# currentHack.net
KiCad netlist of a schematic drawn in EAGLE
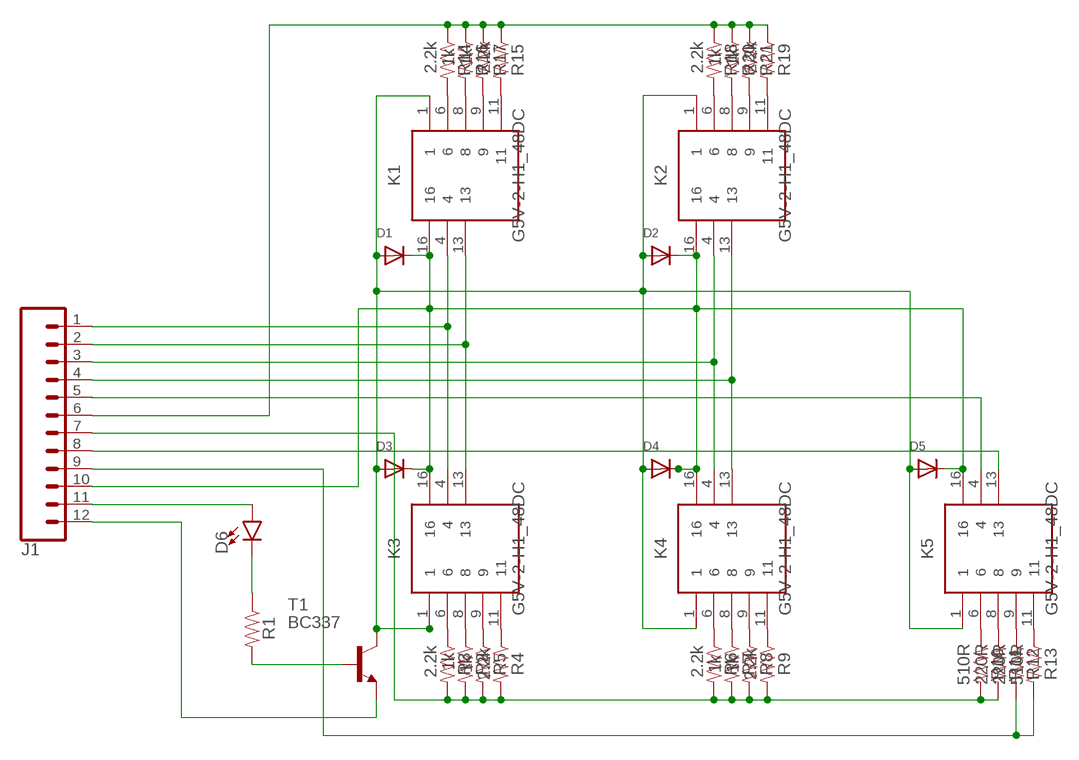
[diagram p0: schematic, sheet 1]

(export (version "E")
  (design (tool "Eeschema 10.0.6"))
  (components
    (comp (ref "D1")
      (value "DIODEDO-1N4148")
      (footprint "eagle-import:DO-1N4148")
      (libsource (lib "eagle-import") (part "DIODEDO-1N4148"))
    )
    (comp (ref "D2")
      (value "DIODEDO-1N4148")
      (footprint "eagle-import:DO-1N4148")
      (libsource (lib "eagle-import") (part "DIODEDO-1N4148"))
    )
    (comp (ref "D3")
      (value "DIODEDO-1N4148")
      (footprint "eagle-import:DO-1N4148")
      (libsource (lib "eagle-import") (part "DIODEDO-1N4148"))
    )
    (comp (ref "D4")
      (value "DIODEDO-1N4148")
      (footprint "eagle-import:DO-1N4148")
      (libsource (lib "eagle-import") (part "DIODEDO-1N4148"))
    )
    (comp (ref "D5")
      (value "DIODEDO-1N4148")
      (footprint "eagle-import:DO-1N4148")
      (libsource (lib "eagle-import") (part "DIODEDO-1N4148"))
    )
    (comp (ref "D6")
      (value "LED3MM")
      (footprint "eagle-import:LED_3MM")
      (libsource (lib "eagle-import") (part "LED3MM"))
    )
    (comp (ref "J1")
      (value "CONN_12")
      (footprint "eagle-import:1X12")
      (libsource (lib "eagle-import") (part "CONN_12"))
    )
    (comp (ref "K1")
      (value "G5V-2-H1_48DC")
      (footprint "eagle-import:G5V-2-H1")
      (fields
        (field (name "MANUFACTURER_PART_NUMBER") "G5V-2-H1 48DC")
        (field (name "RS_PART_NUMBER") "6839270P")
      )
      (libsource (lib "eagle-import") (part "G5V-2-H1_48DC"))
    )
    (comp (ref "K2")
      (value "G5V-2-H1_48DC")
      (footprint "eagle-import:G5V-2-H1")
      (fields
        (field (name "MANUFACTURER_PART_NUMBER") "G5V-2-H1 48DC")
        (field (name "RS_PART_NUMBER") "6839270P")
      )
      (libsource (lib "eagle-import") (part "G5V-2-H1_48DC"))
    )
    (comp (ref "K3")
      (value "G5V-2-H1_48DC")
      (footprint "eagle-import:G5V-2-H1")
      (fields
        (field (name "MANUFACTURER_PART_NUMBER") "G5V-2-H1 48DC")
        (field (name "RS_PART_NUMBER") "6839270P")
      )
      (libsource (lib "eagle-import") (part "G5V-2-H1_48DC"))
    )
    (comp (ref "K4")
      (value "G5V-2-H1_48DC")
      (footprint "eagle-import:G5V-2-H1")
      (fields
        (field (name "MANUFACTURER_PART_NUMBER") "G5V-2-H1 48DC")
        (field (name "RS_PART_NUMBER") "6839270P")
      )
      (libsource (lib "eagle-import") (part "G5V-2-H1_48DC"))
    )
    (comp (ref "K5")
      (value "G5V-2-H1_48DC")
      (footprint "eagle-import:G5V-2-H1")
      (fields
        (field (name "MANUFACTURER_PART_NUMBER") "G5V-2-H1 48DC")
        (field (name "RS_PART_NUMBER") "6839270P")
      )
      (libsource (lib "eagle-import") (part "G5V-2-H1_48DC"))
    )
    (comp (ref "R1")
      (value "RESISTORAXIAL-0.3")
      (footprint "eagle-import:AXIAL-0.3")
      (libsource (lib "eagle-import") (part "RESISTORAXIAL-0.3"))
    )
    (comp (ref "R2")
      (value "1k")
      (footprint "eagle-import:AXIAL-0.3")
      (libsource (lib "eagle-import") (part "RESISTORAXIAL-0.3"))
    )
    (comp (ref "R3")
      (value "2.2k")
      (footprint "eagle-import:AXIAL-0.3")
      (libsource (lib "eagle-import") (part "RESISTORAXIAL-0.3"))
    )
    (comp (ref "R4")
      (value "2.2k")
      (footprint "eagle-import:AXIAL-0.3")
      (libsource (lib "eagle-import") (part "RESISTORAXIAL-0.3"))
    )
    (comp (ref "R5")
      (value "1k")
      (footprint "eagle-import:AXIAL-0.3")
      (libsource (lib "eagle-import") (part "RESISTORAXIAL-0.3"))
    )
    (comp (ref "R6")
      (value "2.2k")
      (footprint "eagle-import:AXIAL-0.3")
      (libsource (lib "eagle-import") (part "RESISTORAXIAL-0.3"))
    )
    (comp (ref "R7")
      (value "1k")
      (footprint "eagle-import:AXIAL-0.3")
      (libsource (lib "eagle-import") (part "RESISTORAXIAL-0.3"))
    )
    (comp (ref "R8")
      (value "1k")
      (footprint "eagle-import:AXIAL-0.3")
      (libsource (lib "eagle-import") (part "RESISTORAXIAL-0.3"))
    )
    (comp (ref "R9")
      (value "2.2k")
      (footprint "eagle-import:AXIAL-0.3")
      (libsource (lib "eagle-import") (part "RESISTORAXIAL-0.3"))
    )
    (comp (ref "R10")
      (value "510R")
      (footprint "eagle-import:AXIAL-0.3")
      (libsource (lib "eagle-import") (part "RESISTORAXIAL-0.3"))
    )
    (comp (ref "R11")
      (value "220R")
      (footprint "eagle-import:AXIAL-0.3")
      (libsource (lib "eagle-import") (part "RESISTORAXIAL-0.3"))
    )
    (comp (ref "R12")
      (value "220R")
      (footprint "eagle-import:AXIAL-0.3")
      (libsource (lib "eagle-import") (part "RESISTORAXIAL-0.3"))
    )
    (comp (ref "R13")
      (value "510R")
      (footprint "eagle-import:AXIAL-0.3")
      (libsource (lib "eagle-import") (part "RESISTORAXIAL-0.3"))
    )
    (comp (ref "R14")
      (value "2.2k")
      (footprint "eagle-import:AXIAL-0.3")
      (libsource (lib "eagle-import") (part "RESISTORAXIAL-0.3"))
    )
    (comp (ref "R15")
      (value "2.2k")
      (footprint "eagle-import:AXIAL-0.3")
      (libsource (lib "eagle-import") (part "RESISTORAXIAL-0.3"))
    )
    (comp (ref "R16")
      (value "1k")
      (footprint "eagle-import:AXIAL-0.3")
      (libsource (lib "eagle-import") (part "RESISTORAXIAL-0.3"))
    )
    (comp (ref "R17")
      (value "1k")
      (footprint "eagle-import:AXIAL-0.3")
      (libsource (lib "eagle-import") (part "RESISTORAXIAL-0.3"))
    )
    (comp (ref "R18")
      (value "2.2k")
      (footprint "eagle-import:AXIAL-0.3")
      (libsource (lib "eagle-import") (part "RESISTORAXIAL-0.3"))
    )
    (comp (ref "R19")
      (value "2.2k")
      (footprint "eagle-import:AXIAL-0.3")
      (libsource (lib "eagle-import") (part "RESISTORAXIAL-0.3"))
    )
    (comp (ref "R20")
      (value "1k")
      (footprint "eagle-import:AXIAL-0.3")
      (libsource (lib "eagle-import") (part "RESISTORAXIAL-0.3"))
    )
    (comp (ref "R21")
      (value "1k")
      (footprint "eagle-import:AXIAL-0.3")
      (libsource (lib "eagle-import") (part "RESISTORAXIAL-0.3"))
    )
    (comp (ref "T1")
      (value "BC337")
      (footprint "eagle-import:TO92")
      (libsource (lib "eagle-import") (part "BC337"))
    )
  )
  (nets
    (net (code "1") (name "Net-(D1-PadC)") (class "Default")
      (node (ref "D1") (pin "C") (pinfunction "C_C") (pintype "passive"))
      (node (ref "D2") (pin "C") (pinfunction "C_C") (pintype "passive"))
      (node (ref "D3") (pin "C") (pinfunction "C_C") (pintype "passive"))
      (node (ref "D4") (pin "C") (pinfunction "C_C") (pintype "passive"))
      (node (ref "D5") (pin "C") (pinfunction "C_C") (pintype "passive"))
      (node (ref "J1") (pin "10") (pinfunction "10_10") (pintype "passive"))
      (node (ref "K1") (pin "16") (pinfunction "16_16") (pintype "passive"))
      (node (ref "K2") (pin "16") (pinfunction "16_16") (pintype "passive"))
      (node (ref "K3") (pin "16") (pinfunction "16_16") (pintype "passive"))
      (node (ref "K4") (pin "16") (pinfunction "16_16") (pintype "passive"))
      (node (ref "K5") (pin "16") (pinfunction "16_16") (pintype "passive"))
    )
    (net (code "2") (name "Net-(D6-C)") (class "Default")
      (node (ref "D6") (pin "K") (pinfunction "C_K") (pintype "passive"))
      (node (ref "R1") (pin "P$1") (pinfunction "1_P$1") (pintype "passive"))
    )
    (net (code "3") (name "Net-(D6-PadA)") (class "Default")
      (node (ref "D6") (pin "A") (pinfunction "A_A") (pintype "passive"))
      (node (ref "J1") (pin "11") (pinfunction "11_11") (pintype "passive"))
    )
    (net (code "4") (name "Net-(J1-Pad1)") (class "Default")
      (node (ref "J1") (pin "1") (pinfunction "1_1") (pintype "passive"))
      (node (ref "K1") (pin "4") (pinfunction "4_4") (pintype "passive"))
      (node (ref "K3") (pin "4") (pinfunction "4_4") (pintype "passive"))
    )
    (net (code "5") (name "Net-(J1-Pad2)") (class "Default")
      (node (ref "J1") (pin "2") (pinfunction "2_2") (pintype "passive"))
      (node (ref "K1") (pin "13") (pinfunction "13_13") (pintype "passive"))
      (node (ref "K3") (pin "13") (pinfunction "13_13") (pintype "passive"))
    )
    (net (code "6") (name "Net-(J1-Pad3)") (class "Default")
      (node (ref "J1") (pin "3") (pinfunction "3_3") (pintype "passive"))
      (node (ref "K2") (pin "4") (pinfunction "4_4") (pintype "passive"))
      (node (ref "K4") (pin "4") (pinfunction "4_4") (pintype "passive"))
    )
    (net (code "7") (name "Net-(J1-Pad4)") (class "Default")
      (node (ref "J1") (pin "4") (pinfunction "4_4") (pintype "passive"))
      (node (ref "K2") (pin "13") (pinfunction "13_13") (pintype "passive"))
      (node (ref "K4") (pin "13") (pinfunction "13_13") (pintype "passive"))
    )
    (net (code "8") (name "Net-(J1-Pad5)") (class "Default")
      (node (ref "J1") (pin "5") (pinfunction "5_5") (pintype "passive"))
      (node (ref "K5") (pin "4") (pinfunction "4_4") (pintype "passive"))
    )
    (net (code "9") (name "Net-(J1-Pad8)") (class "Default")
      (node (ref "J1") (pin "8") (pinfunction "8_8") (pintype "passive"))
      (node (ref "K5") (pin "13") (pinfunction "13_13") (pintype "passive"))
    )
    (net (code "10") (name "Net-(R1-2)") (class "Default")
      (node (ref "R1") (pin "P$2") (pinfunction "2_P$2") (pintype "passive"))
      (node (ref "T1") (pin "2") (pinfunction "B_2") (pintype "passive"))
    )
    (net (code "11") (name "Net-(R2-1)") (class "Default")
      (node (ref "K3") (pin "8") (pinfunction "8_8") (pintype "passive"))
      (node (ref "R2") (pin "P$1") (pinfunction "1_P$1") (pintype "passive"))
    )
    (net (code "12") (name "Net-(R3-1)") (class "Default")
      (node (ref "K3") (pin "6") (pinfunction "6_6") (pintype "passive"))
      (node (ref "R3") (pin "P$1") (pinfunction "1_P$1") (pintype "passive"))
    )
    (net (code "13") (name "Net-(R4-1)") (class "Default")
      (node (ref "K3") (pin "11") (pinfunction "11_11") (pintype "passive"))
      (node (ref "R4") (pin "P$1") (pinfunction "1_P$1") (pintype "passive"))
    )
    (net (code "14") (name "Net-(R5-1)") (class "Default")
      (node (ref "K3") (pin "9") (pinfunction "9_9") (pintype "passive"))
      (node (ref "R5") (pin "P$1") (pinfunction "1_P$1") (pintype "passive"))
    )
    (net (code "15") (name "Net-(R6-1)") (class "Default")
      (node (ref "K4") (pin "6") (pinfunction "6_6") (pintype "passive"))
      (node (ref "R6") (pin "P$1") (pinfunction "1_P$1") (pintype "passive"))
    )
    (net (code "16") (name "Net-(R7-1)") (class "Default")
      (node (ref "K4") (pin "8") (pinfunction "8_8") (pintype "passive"))
      (node (ref "R7") (pin "P$1") (pinfunction "1_P$1") (pintype "passive"))
    )
    (net (code "17") (name "Net-(R8-1)") (class "Default")
      (node (ref "K4") (pin "9") (pinfunction "9_9") (pintype "passive"))
      (node (ref "R8") (pin "P$1") (pinfunction "1_P$1") (pintype "passive"))
    )
    (net (code "18") (name "Net-(R9-1)") (class "Default")
      (node (ref "K4") (pin "11") (pinfunction "11_11") (pintype "passive"))
      (node (ref "R9") (pin "P$1") (pinfunction "1_P$1") (pintype "passive"))
    )
    (net (code "19") (name "Net-(R10-1)") (class "Default")
      (node (ref "K5") (pin "6") (pinfunction "6_6") (pintype "passive"))
      (node (ref "R10") (pin "P$1") (pinfunction "1_P$1") (pintype "passive"))
    )
    (net (code "20") (name "Net-(R10-2)") (class "Default")
      (node (ref "J1") (pin "7") (pinfunction "7_7") (pintype "passive"))
      (node (ref "R10") (pin "P$2") (pinfunction "2_P$2") (pintype "passive"))
      (node (ref "R11") (pin "P$2") (pinfunction "2_P$2") (pintype "passive"))
      (node (ref "R2") (pin "P$2") (pinfunction "2_P$2") (pintype "passive"))
      (node (ref "R3") (pin "P$2") (pinfunction "2_P$2") (pintype "passive"))
      (node (ref "R4") (pin "P$2") (pinfunction "2_P$2") (pintype "passive"))
      (node (ref "R5") (pin "P$2") (pinfunction "2_P$2") (pintype "passive"))
      (node (ref "R6") (pin "P$2") (pinfunction "2_P$2") (pintype "passive"))
      (node (ref "R7") (pin "P$2") (pinfunction "2_P$2") (pintype "passive"))
      (node (ref "R8") (pin "P$2") (pinfunction "2_P$2") (pintype "passive"))
      (node (ref "R9") (pin "P$2") (pinfunction "2_P$2") (pintype "passive"))
    )
    (net (code "21") (name "Net-(R11-1)") (class "Default")
      (node (ref "K5") (pin "8") (pinfunction "8_8") (pintype "passive"))
      (node (ref "R11") (pin "P$1") (pinfunction "1_P$1") (pintype "passive"))
    )
    (net (code "22") (name "Net-(R12-1)") (class "Default")
      (node (ref "K5") (pin "9") (pinfunction "9_9") (pintype "passive"))
      (node (ref "R12") (pin "P$1") (pinfunction "1_P$1") (pintype "passive"))
    )
    (net (code "23") (name "Net-(R12-2)") (class "Default")
      (node (ref "J1") (pin "9") (pinfunction "9_9") (pintype "passive"))
      (node (ref "R12") (pin "P$2") (pinfunction "2_P$2") (pintype "passive"))
      (node (ref "R13") (pin "P$2") (pinfunction "2_P$2") (pintype "passive"))
    )
    (net (code "24") (name "Net-(R13-1)") (class "Default")
      (node (ref "K5") (pin "11") (pinfunction "11_11") (pintype "passive"))
      (node (ref "R13") (pin "P$1") (pinfunction "1_P$1") (pintype "passive"))
    )
    (net (code "25") (name "Net-(R14-1)") (class "Default")
      (node (ref "J1") (pin "6") (pinfunction "6_6") (pintype "passive"))
      (node (ref "R14") (pin "P$1") (pinfunction "1_P$1") (pintype "passive"))
      (node (ref "R15") (pin "P$1") (pinfunction "1_P$1") (pintype "passive"))
      (node (ref "R16") (pin "P$1") (pinfunction "1_P$1") (pintype "passive"))
      (node (ref "R17") (pin "P$1") (pinfunction "1_P$1") (pintype "passive"))
      (node (ref "R18") (pin "P$1") (pinfunction "1_P$1") (pintype "passive"))
      (node (ref "R19") (pin "P$1") (pinfunction "1_P$1") (pintype "passive"))
      (node (ref "R20") (pin "P$1") (pinfunction "1_P$1") (pintype "passive"))
      (node (ref "R21") (pin "P$1") (pinfunction "1_P$1") (pintype "passive"))
    )
    (net (code "26") (name "Net-(R14-2)") (class "Default")
      (node (ref "K1") (pin "6") (pinfunction "6_6") (pintype "passive"))
      (node (ref "R14") (pin "P$2") (pinfunction "2_P$2") (pintype "passive"))
    )
    (net (code "27") (name "Net-(R15-2)") (class "Default")
      (node (ref "K1") (pin "11") (pinfunction "11_11") (pintype "passive"))
      (node (ref "R15") (pin "P$2") (pinfunction "2_P$2") (pintype "passive"))
    )
    (net (code "28") (name "Net-(R16-2)") (class "Default")
      (node (ref "K1") (pin "8") (pinfunction "8_8") (pintype "passive"))
      (node (ref "R16") (pin "P$2") (pinfunction "2_P$2") (pintype "passive"))
    )
    (net (code "29") (name "Net-(R17-2)") (class "Default")
      (node (ref "K1") (pin "9") (pinfunction "9_9") (pintype "passive"))
      (node (ref "R17") (pin "P$2") (pinfunction "2_P$2") (pintype "passive"))
    )
    (net (code "30") (name "Net-(R18-2)") (class "Default")
      (node (ref "K2") (pin "6") (pinfunction "6_6") (pintype "passive"))
      (node (ref "R18") (pin "P$2") (pinfunction "2_P$2") (pintype "passive"))
    )
    (net (code "31") (name "Net-(R19-2)") (class "Default")
      (node (ref "K2") (pin "11") (pinfunction "11_11") (pintype "passive"))
      (node (ref "R19") (pin "P$2") (pinfunction "2_P$2") (pintype "passive"))
    )
    (net (code "32") (name "Net-(R20-2)") (class "Default")
      (node (ref "K2") (pin "8") (pinfunction "8_8") (pintype "passive"))
      (node (ref "R20") (pin "P$2") (pinfunction "2_P$2") (pintype "passive"))
    )
    (net (code "33") (name "Net-(R21-2)") (class "Default")
      (node (ref "K2") (pin "9") (pinfunction "9_9") (pintype "passive"))
      (node (ref "R21") (pin "P$2") (pinfunction "2_P$2") (pintype "passive"))
    )
    (net (code "34") (name "Net-(T1-C)") (class "Default")
      (node (ref "D1") (pin "A") (pinfunction "A_A") (pintype "passive"))
      (node (ref "D2") (pin "A") (pinfunction "A_A") (pintype "passive"))
      (node (ref "D3") (pin "A") (pinfunction "A_A") (pintype "passive"))
      (node (ref "D4") (pin "A") (pinfunction "A_A") (pintype "passive"))
      (node (ref "D5") (pin "A") (pinfunction "A_A") (pintype "passive"))
      (node (ref "K1") (pin "1") (pinfunction "1_1") (pintype "passive"))
      (node (ref "K2") (pin "1") (pinfunction "1_1") (pintype "passive"))
      (node (ref "K3") (pin "1") (pinfunction "1_1") (pintype "passive"))
      (node (ref "K4") (pin "1") (pinfunction "1_1") (pintype "passive"))
      (node (ref "K5") (pin "1") (pinfunction "1_1") (pintype "passive"))
      (node (ref "T1") (pin "3") (pinfunction "C_3") (pintype "passive"))
    )
    (net (code "35") (name "Net-(T1-E)") (class "Default")
      (node (ref "J1") (pin "12") (pinfunction "12_12") (pintype "passive"))
      (node (ref "T1") (pin "1") (pinfunction "E_1") (pintype "passive"))
    )
  )
)
